# GeneralPortBreakout.net
KiCad netlist of a schematic drawn in EasyEDA
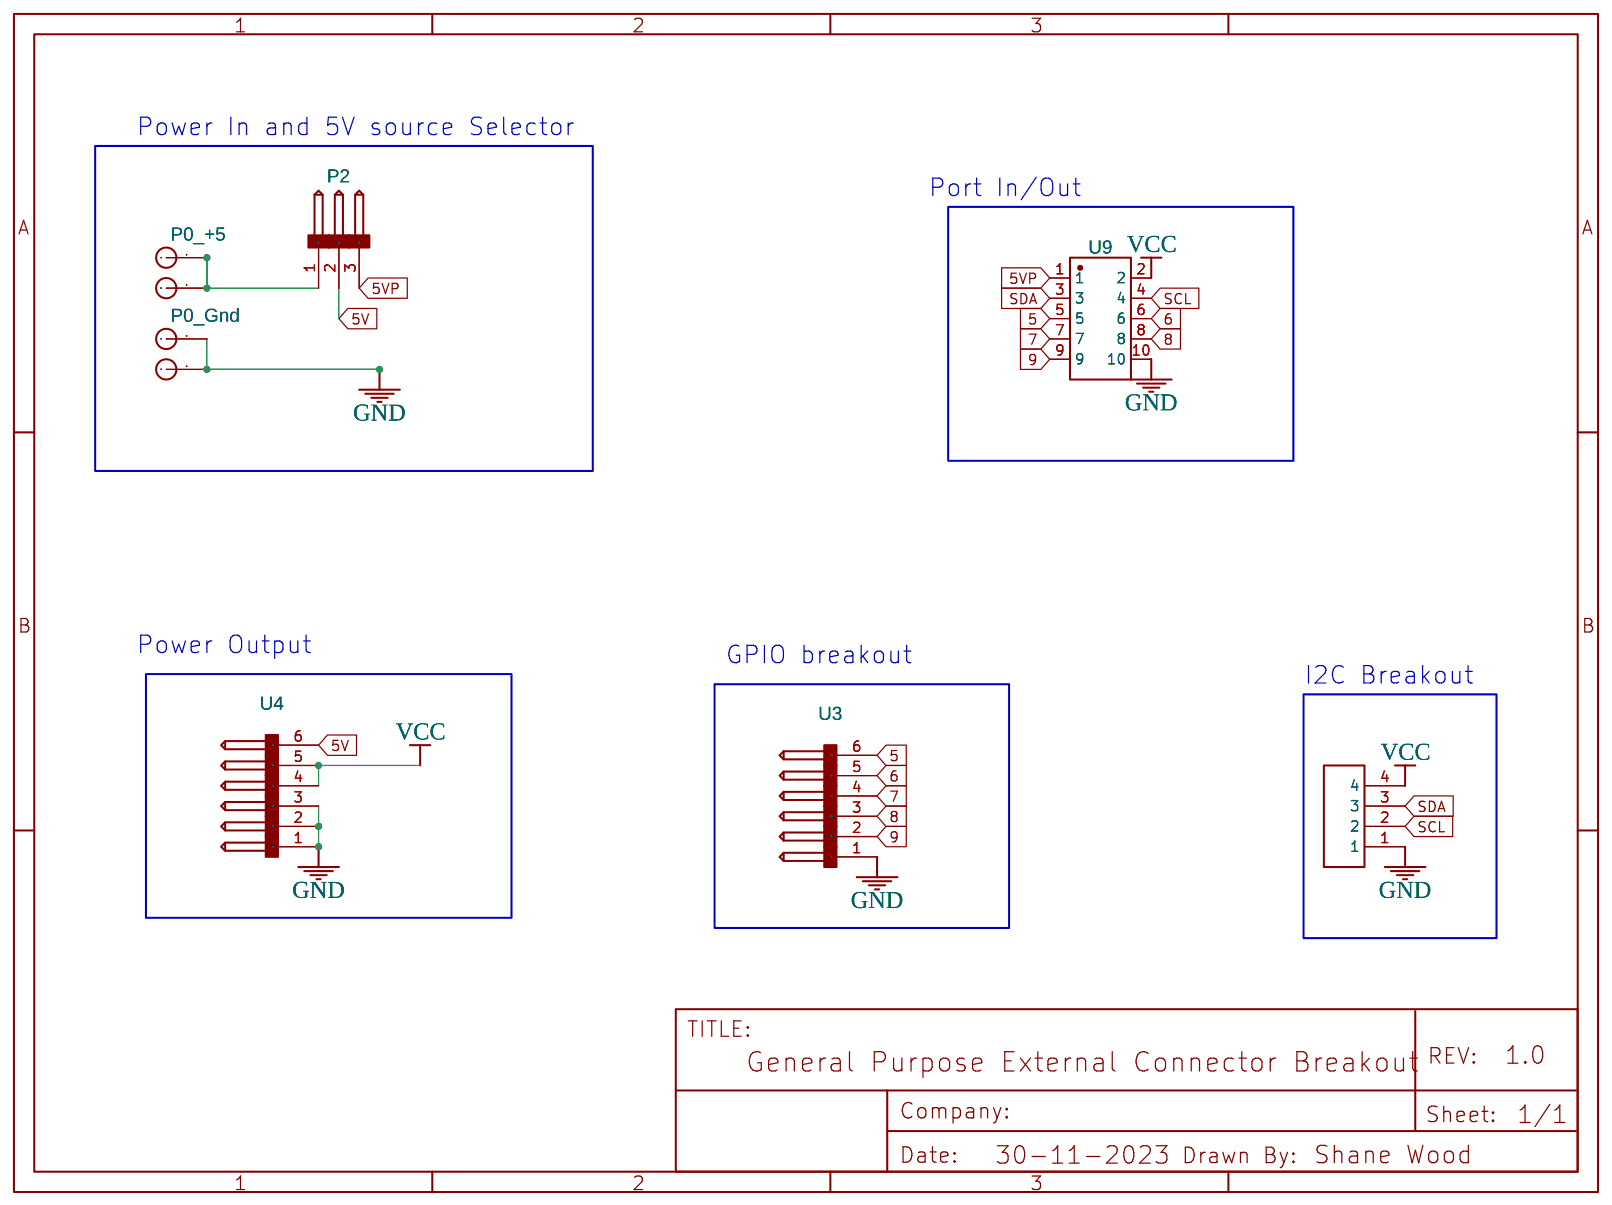
[diagram p0: schematic sheet]

(export (version "E")
  (design (tool "Eeschema 10.0.6"))
  (components
    (comp (ref "P1") (value "Connector_1x4/2.5mm") (libsource (lib "") (part "Connector_1x4/2.5mm")))
    (comp (ref "P2") (value "HDR-PIN-MALE-2.54-1x3") (libsource (lib "") (part "HDR-PIN-MALE-2.54-1x3")))
    (comp (ref "U1")
      (value "NO")
      (fields (field (name "Manufacturer Part") "Wire Hole"))
      (libsource (lib "") (part "Wire Hole 14AWG"))
    )
    (comp (ref "U2")
      (value "P0_+5")
      (fields (field (name "Manufacturer Part") "Wire Hole"))
      (libsource (lib "") (part "Wire Hole 14AWG"))
    )
    (comp (ref "U3") (value "NO") (libsource (lib "") (part "HDR-PIN-MALE-2.54-1x6")))
    (comp (ref "U4") (value "NO") (libsource (lib "") (part "HDR-PIN-MALE-2.54-1x6")))
    (comp (ref "U5")
      (value "NO")
      (fields (field (name "Manufacturer Part") "Wire Hole"))
      (libsource (lib "") (part "Wire Hole 14AWG"))
    )
    (comp (ref "U6")
      (value "P0_Gnd")
      (fields (field (name "Manufacturer Part") "Wire Hole"))
      (libsource (lib "") (part "Wire Hole 14AWG"))
    )
    (comp (ref "U9")
      (value "NO")
      (fields
        (field (name "Manufacturer Part") "KH-2.54PH180-2X5P-L8.9")
        (field (name "Manufacturer") "kinghelm(金航标)")
      )
      (libsource (lib "") (part "KH-2.54PH180-2X5P"))
    )
  )
  (nets
    (net (code "1") (name "5") (class "Default")
      (node (ref "U3") (pin "6") (pinfunction "6_6") (pintype "input"))
      (node (ref "U9") (pin "5") (pinfunction "5_5") (pintype "unspecified"))
    )
    (net (code "2") (name "5V") (class "Default")
      (node (ref "P2") (pin "2") (pinfunction "2_2") (pintype "input"))
      (node (ref "U4") (pin "6") (pinfunction "6_6") (pintype "input"))
    )
    (net (code "3") (name "5VP") (class "Default")
      (node (ref "P2") (pin "3") (pinfunction "3_3") (pintype "input"))
      (node (ref "U9") (pin "1") (pinfunction "1_1") (pintype "unspecified"))
    )
    (net (code "4") (name "6") (class "Default")
      (node (ref "U3") (pin "5") (pinfunction "5_5") (pintype "input"))
      (node (ref "U9") (pin "6") (pinfunction "6_6") (pintype "unspecified"))
    )
    (net (code "5") (name "7") (class "Default")
      (node (ref "U3") (pin "4") (pinfunction "4_4") (pintype "input"))
      (node (ref "U9") (pin "7") (pinfunction "7_7") (pintype "unspecified"))
    )
    (net (code "6") (name "8") (class "Default")
      (node (ref "U3") (pin "3") (pinfunction "3_3") (pintype "input"))
      (node (ref "U9") (pin "8") (pinfunction "8_8") (pintype "unspecified"))
    )
    (net (code "7") (name "9") (class "Default")
      (node (ref "U3") (pin "2") (pinfunction "2_2") (pintype "input"))
      (node (ref "U9") (pin "9") (pinfunction "9_9") (pintype "unspecified"))
    )
    (net (code "8") (name "GND") (class "Default")
      (node (ref "P1") (pin "1") (pinfunction "1_1") (pintype "unspecified"))
      (node (ref "U3") (pin "1") (pinfunction "1_1") (pintype "input"))
      (node (ref "U4") (pin "1") (pinfunction "1_1") (pintype "input"))
      (node (ref "U4") (pin "2") (pinfunction "2_2") (pintype "input"))
      (node (ref "U4") (pin "3") (pinfunction "3_3") (pintype "input"))
      (node (ref "U5") (pin "1") (pinfunction "1_1") (pintype "unspecified"))
      (node (ref "U6") (pin "1") (pinfunction "1_1") (pintype "unspecified"))
      (node (ref "U9") (pin "10") (pinfunction "10_10") (pintype "unspecified"))
    )
    (net (code "9") (name "Net-(P2-Pad1)") (class "Default")
      (node (ref "P2") (pin "1") (pinfunction "1_1") (pintype "input"))
      (node (ref "U1") (pin "1") (pinfunction "1_1") (pintype "unspecified"))
      (node (ref "U2") (pin "1") (pinfunction "1_1") (pintype "unspecified"))
    )
    (net (code "10") (name "SCL") (class "Default")
      (node (ref "P1") (pin "2") (pinfunction "2_2") (pintype "unspecified"))
      (node (ref "U9") (pin "4") (pinfunction "4_4") (pintype "unspecified"))
    )
    (net (code "11") (name "SDA") (class "Default")
      (node (ref "P1") (pin "3") (pinfunction "3_3") (pintype "unspecified"))
      (node (ref "U9") (pin "3") (pinfunction "3_3") (pintype "unspecified"))
    )
    (net (code "12") (name "VCC") (class "Default")
      (node (ref "P1") (pin "4") (pinfunction "4_4") (pintype "unspecified"))
      (node (ref "U4") (pin "4") (pinfunction "4_4") (pintype "input"))
      (node (ref "U4") (pin "5") (pinfunction "5_5") (pintype "input"))
      (node (ref "U9") (pin "2") (pinfunction "2_2") (pintype "unspecified"))
    )
  )
)
